# main.net
KiCad netlist of a schematic drawn in EAGLE
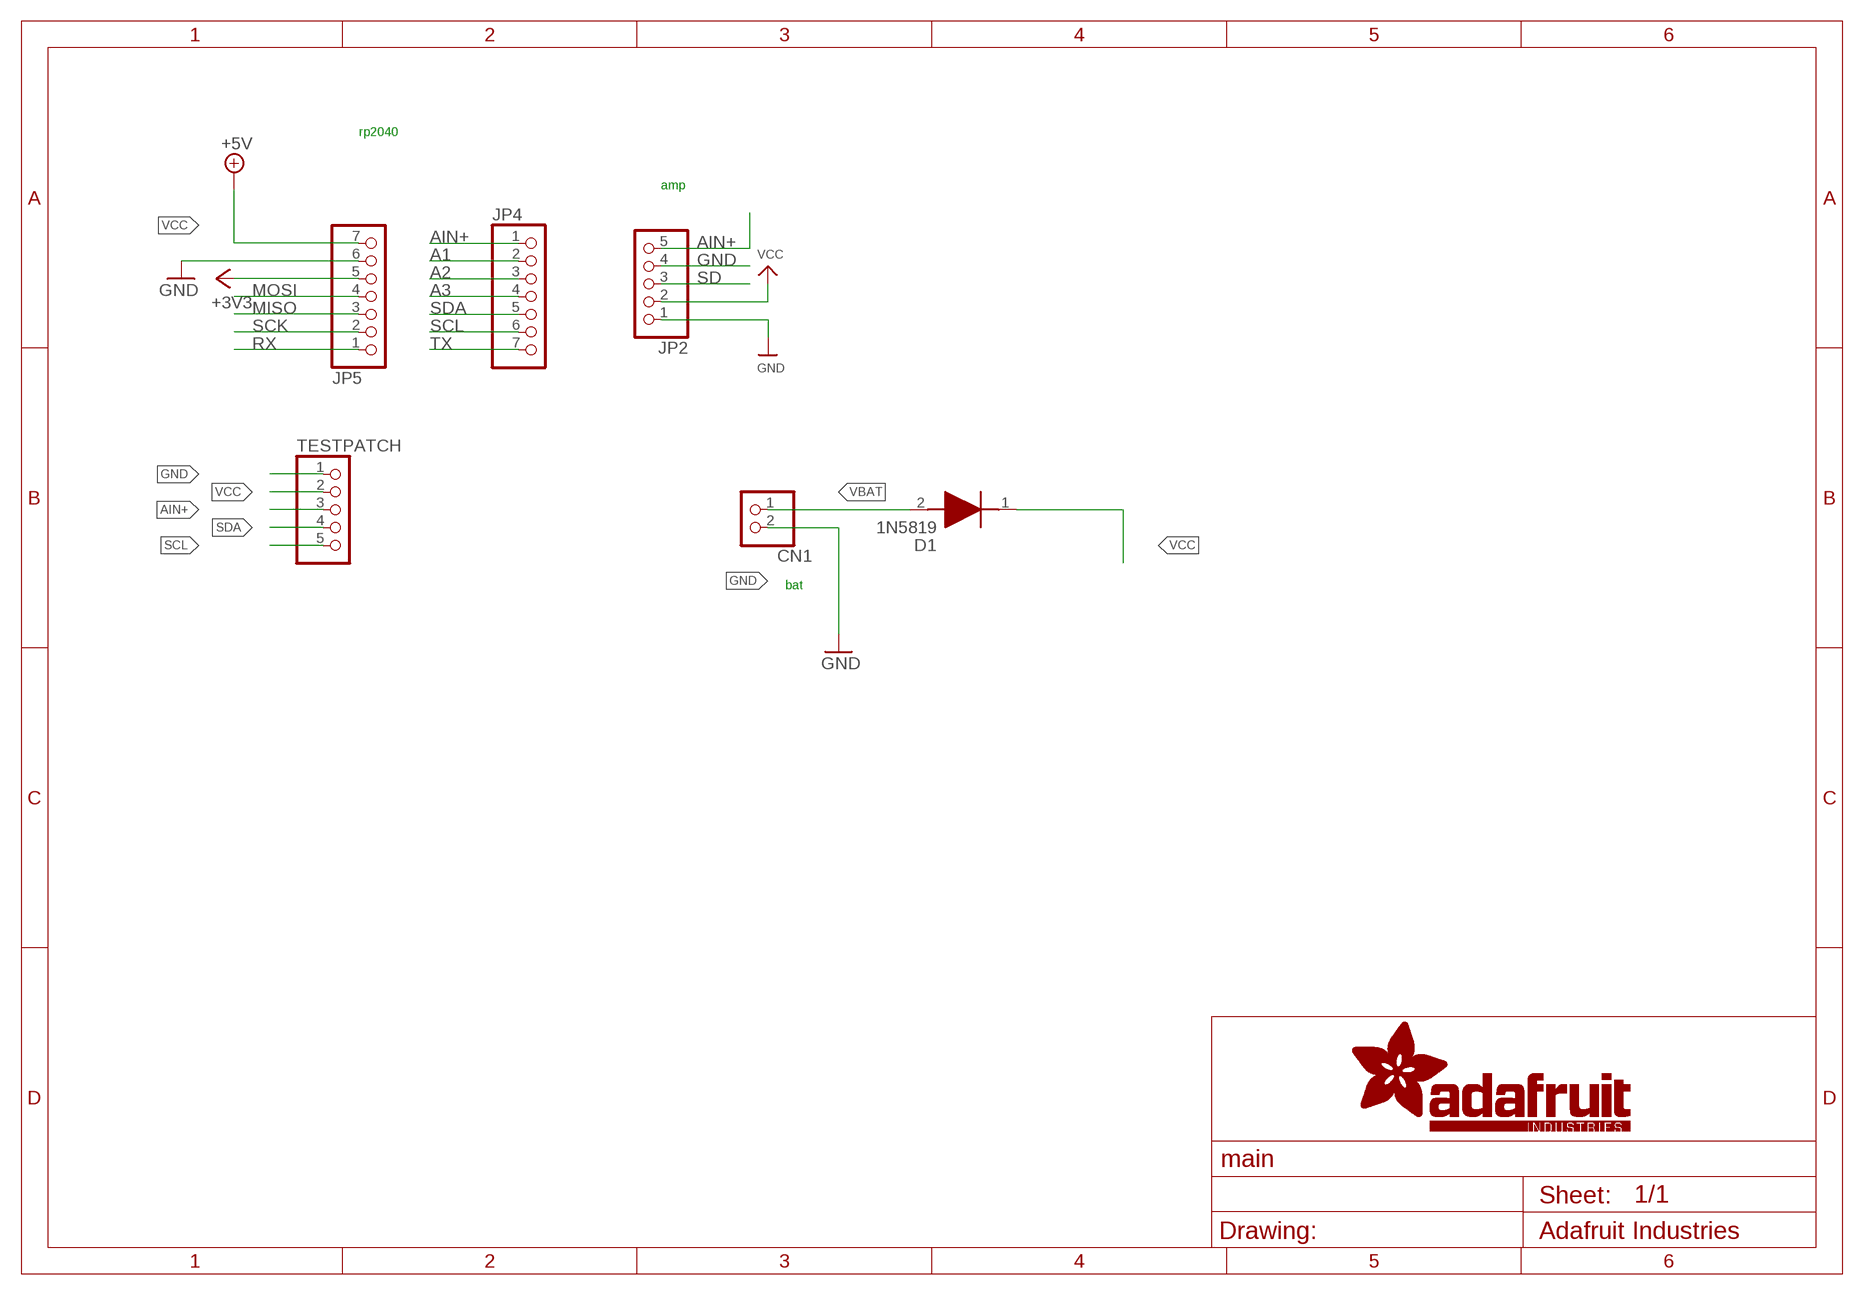
[diagram p0: schematic, sheet 1]

(export (version "E")
  (design (tool "Eeschema 10.0.6"))
  (components
    (comp (ref "CN1")
      (value "JST_2PIN-THM")
      (footprint "eagle-import:JST-PH-2-THM")
      (libsource (lib "eagle-import") (part "JST_2PIN-THM"))
    )
    (comp (ref "D1")
      (value "1N5819")
      (footprint "eagle-import:DIOAD1414W86L464D238")
      (fields (field (name "RS_PART_NUMBER") "4864460P"))
      (libsource (lib "eagle-import") (part "1N5819"))
    )
    (comp (ref "JP2")
      (value "HEADER-1X570MIL")
      (footprint "eagle-import:1X05_ROUND_70")
      (libsource (lib "eagle-import") (part "HEADER-1X570MIL"))
    )
    (comp (ref "JP4")
      (value "HEADER-1X7")
      (footprint "eagle-import:1X07_OVAL")
      (libsource (lib "eagle-import") (part "HEADER-1X7"))
    )
    (comp (ref "JP5")
      (value "HEADER-1X7")
      (footprint "eagle-import:1X07_OVAL")
      (libsource (lib "eagle-import") (part "HEADER-1X7"))
    )
    (comp (ref "TESTPATCH")
      (value "PINHD-1X5")
      (footprint "eagle-import:1X05")
      (libsource (lib "eagle-import") (part "PINHD-1X5"))
    )
  )
  (nets
    (net (code "1") (name "+3V3") (class "Default")
      (node (ref "JP5") (pin "5") (pinfunction "5_5") (pintype "passive"))
    )
    (net (code "2") (name "/A1") (class "Default")
      (node (ref "JP4") (pin "2") (pinfunction "2_2") (pintype "passive"))
    )
    (net (code "3") (name "/A2") (class "Default")
      (node (ref "JP4") (pin "3") (pinfunction "3_3") (pintype "passive"))
    )
    (net (code "4") (name "/A3") (class "Default")
      (node (ref "JP4") (pin "4") (pinfunction "4_4") (pintype "passive"))
    )
    (net (code "5") (name "/MISO") (class "Default")
      (node (ref "JP5") (pin "3") (pinfunction "3_3") (pintype "passive"))
    )
    (net (code "6") (name "/MOSI") (class "Default")
      (node (ref "JP5") (pin "4") (pinfunction "4_4") (pintype "passive"))
    )
    (net (code "7") (name "/RX") (class "Default")
      (node (ref "JP5") (pin "1") (pinfunction "1_1") (pintype "passive"))
    )
    (net (code "8") (name "/SCK") (class "Default")
      (node (ref "JP5") (pin "2") (pinfunction "2_2") (pintype "passive"))
    )
    (net (code "9") (name "/SD") (class "Default")
      (node (ref "JP2") (pin "3") (pinfunction "3_3") (pintype "passive"))
    )
    (net (code "10") (name "/TX") (class "Default")
      (node (ref "JP4") (pin "7") (pinfunction "7_7") (pintype "passive"))
    )
    (net (code "11") (name "AIN+") (class "Default")
      (node (ref "JP2") (pin "5") (pinfunction "5_5") (pintype "passive"))
      (node (ref "JP4") (pin "1") (pinfunction "1_1") (pintype "passive"))
      (node (ref "TESTPATCH") (pin "3") (pinfunction "3_3") (pintype "passive"))
    )
    (net (code "12") (name "GND") (class "Default")
      (node (ref "CN1") (pin "2") (pinfunction "1_2") (pintype "passive"))
      (node (ref "JP2") (pin "1") (pinfunction "1_1") (pintype "passive"))
      (node (ref "JP2") (pin "4") (pinfunction "4_4") (pintype "passive"))
      (node (ref "JP5") (pin "6") (pinfunction "6_6") (pintype "passive"))
      (node (ref "TESTPATCH") (pin "1") (pinfunction "1_1") (pintype "passive"))
    )
    (net (code "13") (name "SCL") (class "Default")
      (node (ref "JP4") (pin "6") (pinfunction "6_6") (pintype "passive"))
      (node (ref "TESTPATCH") (pin "5") (pinfunction "5_5") (pintype "passive"))
    )
    (net (code "14") (name "SDA") (class "Default")
      (node (ref "JP4") (pin "5") (pinfunction "5_5") (pintype "passive"))
      (node (ref "TESTPATCH") (pin "4") (pinfunction "4_4") (pintype "passive"))
    )
    (net (code "15") (name "VBAT") (class "Default")
      (node (ref "CN1") (pin "1") (pinfunction "2_1") (pintype "passive"))
      (node (ref "D1") (pin "2") (pinfunction "A_2") (pintype "bidirectional"))
    )
    (net (code "16") (name "VCC") (class "Default")
      (node (ref "D1") (pin "1") (pinfunction "K_1") (pintype "bidirectional"))
      (node (ref "JP2") (pin "2") (pinfunction "2_2") (pintype "passive"))
      (node (ref "JP5") (pin "7") (pinfunction "7_7") (pintype "passive"))
      (node (ref "TESTPATCH") (pin "2") (pinfunction "2_2") (pintype "passive"))
    )
  )
)
